# narsil.net
KiCad netlist of a schematic drawn in EAGLE
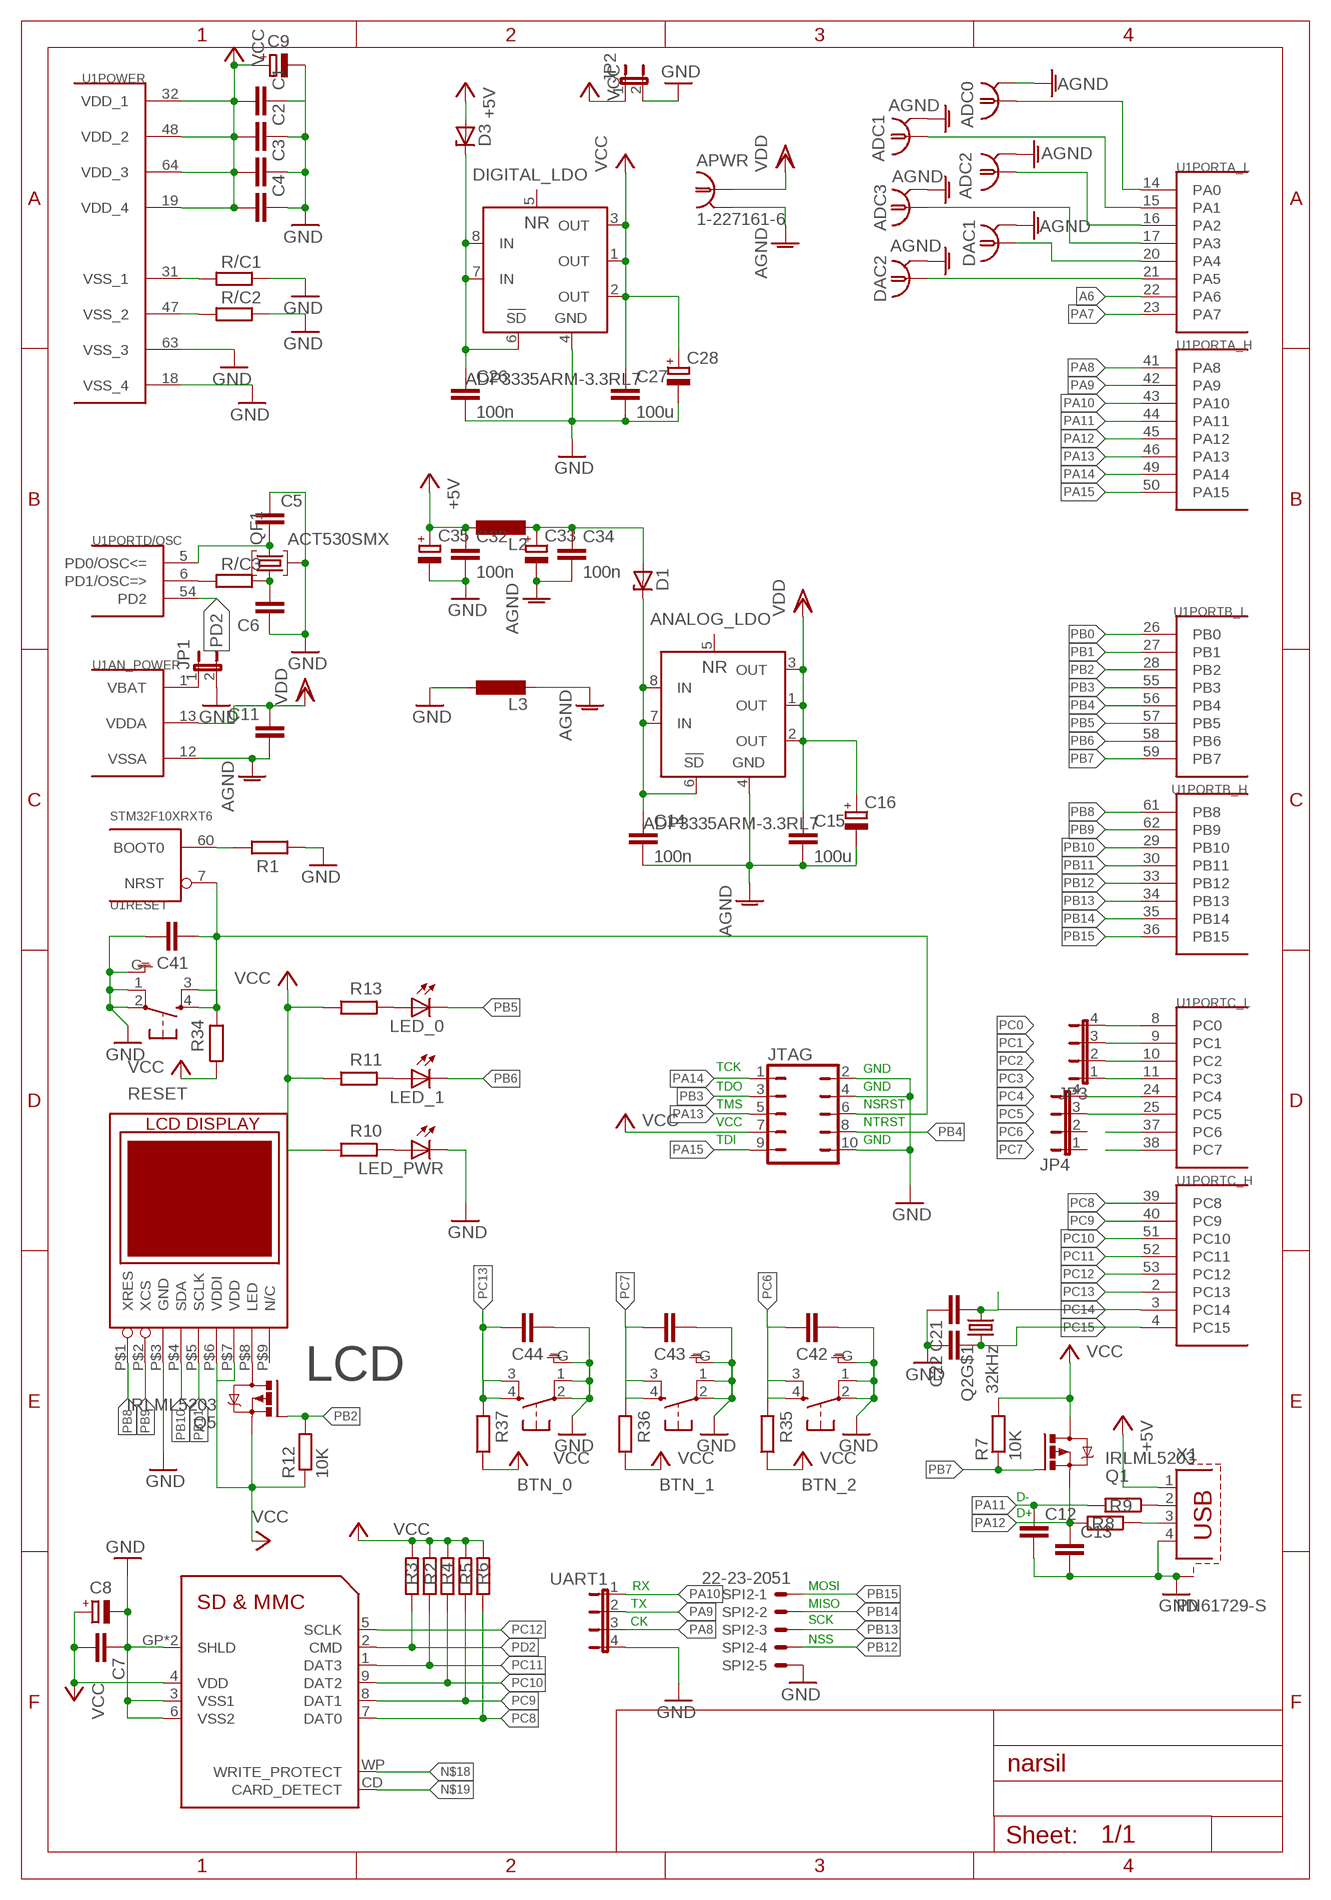
[diagram p0: schematic, sheet 1]

(export (version "E")
  (design (tool "Eeschema 10.0.6"))
  (components
    (comp (ref "ADC0")
      (value "1-227161-6")
      (footprint "eagle-import:AMP_227161")
      (fields (field (name "MF") "TYCO ELECTRONICS"))
      (libsource (lib "eagle-import") (part "?2271611--6"))
    )
    (comp (ref "ADC1")
      (value "1-227161-6")
      (footprint "eagle-import:AMP_227161")
      (fields (field (name "MF") "TYCO ELECTRONICS"))
      (libsource (lib "eagle-import") (part "?2271611--6"))
    )
    (comp (ref "ADC2")
      (value "1-227161-6")
      (footprint "eagle-import:AMP_227161")
      (fields (field (name "MF") "TYCO ELECTRONICS"))
      (libsource (lib "eagle-import") (part "?2271611--6"))
    )
    (comp (ref "ADC3")
      (value "1-227161-6")
      (footprint "eagle-import:AMP_227161")
      (fields
        (field (name "MF") "TYCO ELECTRONICS")
        (field (name "MF_1") "TYCO ELECTRONICS")
        (field (name "MPN") "1-227161-6")
        (field (name "OC_FARNELL") "unknown")
        (field (name "OC_NEWARK") "09H7854")
      )
      (libsource (lib "eagle-import") (part "?2271611--6"))
    )
    (comp (ref "ANALOG_LDO")
      (value "ADP3335ARM-3.3RL7")
      (footprint "eagle-import:MSOP08")
      (libsource (lib "eagle-import") (part "ADP3335ARM-3.3RL7"))
    )
    (comp (ref "APWR")
      (value "1-227161-6")
      (footprint "eagle-import:AMP_227161")
      (fields (field (name "MF") "TYCO ELECTRONICS"))
      (libsource (lib "eagle-import") (part "?2271611--6"))
    )
    (comp (ref "BTN_0")
      (value "10-XXG")
      (footprint "eagle-import:B3F-10XXG")
      (libsource (lib "eagle-import") (part "10-XXG"))
    )
    (comp (ref "BTN_1")
      (value "10-XXG")
      (footprint "eagle-import:B3F-10XXG")
      (libsource (lib "eagle-import") (part "10-XXG"))
    )
    (comp (ref "BTN_2")
      (value "10-XXG")
      (footprint "eagle-import:B3F-10XXG")
      (libsource (lib "eagle-import") (part "10-XXG"))
    )
    (comp (ref "C1")
      (value "C-EUC0805")
      (footprint "eagle-import:C0805")
      (libsource (lib "eagle-import") (part "resistor_C-EUC0805"))
    )
    (comp (ref "C2")
      (value "C-EUC0805")
      (footprint "eagle-import:C0805")
      (libsource (lib "eagle-import") (part "resistor_C-EUC0805"))
    )
    (comp (ref "C3")
      (value "C-EUC0805")
      (footprint "eagle-import:C0805")
      (libsource (lib "eagle-import") (part "resistor_C-EUC0805"))
    )
    (comp (ref "C4")
      (value "C-EUC0805")
      (footprint "eagle-import:C0805")
      (libsource (lib "eagle-import") (part "resistor_C-EUC0805"))
    )
    (comp (ref "C5")
      (value "C-EUC0805")
      (footprint "eagle-import:C0805")
      (libsource (lib "eagle-import") (part "resistor_C-EUC0805"))
    )
    (comp (ref "C6")
      (value "C-EUC0805")
      (footprint "eagle-import:C0805")
      (libsource (lib "eagle-import") (part "resistor_C-EUC0805"))
    )
    (comp (ref "C7")
      (value "C-EUC0805")
      (footprint "eagle-import:C0805")
      (libsource (lib "eagle-import") (part "resistor_C-EUC0805"))
    )
    (comp (ref "C8")
      (value "CPOL-EUSMCA")
      (footprint "eagle-import:SMC_A")
      (libsource (lib "eagle-import") (part "CPOL-EUSMCA"))
    )
    (comp (ref "C9")
      (value "CPOL-EUSMCA")
      (footprint "eagle-import:SMC_A")
      (libsource (lib "eagle-import") (part "CPOL-EUSMCA"))
    )
    (comp (ref "C11")
      (value "C-EUC0805")
      (footprint "eagle-import:C0805")
      (libsource (lib "eagle-import") (part "resistor_C-EUC0805"))
    )
    (comp (ref "C12")
      (value "C-EUC0805")
      (footprint "eagle-import:C0805")
      (libsource (lib "eagle-import") (part "resistor_C-EUC0805"))
    )
    (comp (ref "C13")
      (value "C-EUC0805")
      (footprint "eagle-import:C0805")
      (libsource (lib "eagle-import") (part "resistor_C-EUC0805"))
    )
    (comp (ref "C14")
      (value "100n")
      (footprint "eagle-import:C0805")
      (libsource (lib "eagle-import") (part "C-EUC0805"))
    )
    (comp (ref "C15")
      (value "100u")
      (footprint "eagle-import:C0805")
      (libsource (lib "eagle-import") (part "C-EUC0805"))
    )
    (comp (ref "C16")
      (value "CPOL-EUSMCA")
      (footprint "eagle-import:SMC_A")
      (libsource (lib "eagle-import") (part "CPOL-EUSMCA"))
    )
    (comp (ref "C21")
      (value "C-EUC0805")
      (footprint "eagle-import:C0805")
      (libsource (lib "eagle-import") (part "resistor_C-EUC0805"))
    )
    (comp (ref "C22")
      (value "C-EUC0805")
      (footprint "eagle-import:C0805")
      (libsource (lib "eagle-import") (part "resistor_C-EUC0805"))
    )
    (comp (ref "C26")
      (value "100n")
      (footprint "eagle-import:C0805")
      (libsource (lib "eagle-import") (part "C-EUC0805"))
    )
    (comp (ref "C27")
      (value "100u")
      (footprint "eagle-import:C0805")
      (libsource (lib "eagle-import") (part "C-EUC0805"))
    )
    (comp (ref "C28")
      (value "CPOL-EUSMCA")
      (footprint "eagle-import:SMC_A")
      (libsource (lib "eagle-import") (part "CPOL-EUSMCA"))
    )
    (comp (ref "C32")
      (value "100n")
      (footprint "eagle-import:C0805")
      (libsource (lib "eagle-import") (part "resistor_C-EUC0805"))
    )
    (comp (ref "C33")
      (value "CPOL-EUSMCA")
      (footprint "eagle-import:SMC_A")
      (libsource (lib "eagle-import") (part "CPOL-EUSMCA"))
    )
    (comp (ref "C34")
      (value "100n")
      (footprint "eagle-import:C0805")
      (libsource (lib "eagle-import") (part "resistor_C-EUC0805"))
    )
    (comp (ref "C35")
      (value "CPOL-EUSMCA")
      (footprint "eagle-import:SMC_A")
      (libsource (lib "eagle-import") (part "CPOL-EUSMCA"))
    )
    (comp (ref "C41")
      (value "C-EUC0805")
      (footprint "eagle-import:C0805")
      (libsource (lib "eagle-import") (part "resistor_C-EUC0805"))
    )
    (comp (ref "C42")
      (value "C-EUC0805")
      (footprint "eagle-import:C0805")
      (libsource (lib "eagle-import") (part "resistor_C-EUC0805"))
    )
    (comp (ref "C43")
      (value "C-EUC0805")
      (footprint "eagle-import:C0805")
      (libsource (lib "eagle-import") (part "resistor_C-EUC0805"))
    )
    (comp (ref "C44")
      (value "C-EUC0805")
      (footprint "eagle-import:C0805")
      (libsource (lib "eagle-import") (part "resistor_C-EUC0805"))
    )
    (comp (ref "D1")
      (value "ZENER-DIODESMB")
      (footprint "eagle-import:SMB")
      (libsource (lib "eagle-import") (part "ZENER-DIODESMB"))
    )
    (comp (ref "D3")
      (value "ZENER-DIODESMB")
      (footprint "eagle-import:SMB")
      (libsource (lib "eagle-import") (part "ZENER-DIODESMB"))
    )
    (comp (ref "DAC1")
      (value "1-227161-6")
      (footprint "eagle-import:AMP_227161")
      (fields (field (name "MF") "TYCO ELECTRONICS"))
      (libsource (lib "eagle-import") (part "?2271611--6"))
    )
    (comp (ref "DAC2")
      (value "1-227161-6")
      (footprint "eagle-import:AMP_227161")
      (fields (field (name "MF") "TYCO ELECTRONICS"))
      (libsource (lib "eagle-import") (part "?2271611--6"))
    )
    (comp (ref "DIGITAL_LDO")
      (value "ADP3335ARM-3.3RL7")
      (footprint "eagle-import:MSOP08")
      (libsource (lib "eagle-import") (part "ADP3335ARM-3.3RL7"))
    )
    (comp (ref "JP1")
      (value "JP1E")
      (footprint "eagle-import:JP1")
      (libsource (lib "eagle-import") (part "JP1E"))
    )
    (comp (ref "JP2")
      (value "JP1E")
      (footprint "eagle-import:JP1")
      (libsource (lib "eagle-import") (part "JP1E"))
    )
    (comp (ref "JP3")
      (value "JP4E")
      (footprint "eagle-import:JP4")
      (libsource (lib "eagle-import") (part "JP4E"))
    )
    (comp (ref "JP4")
      (value "JP4E")
      (footprint "eagle-import:JP4")
      (libsource (lib "eagle-import") (part "JP4E"))
    )
    (comp (ref "JTAG")
      (value "JP5Q")
      (footprint "eagle-import:JP5Q")
      (libsource (lib "eagle-import") (part "JP5Q"))
    )
    (comp (ref "L2")
      (value "L-EUL1206")
      (footprint "eagle-import:R1206")
      (libsource (lib "eagle-import") (part "L-EUL1206"))
    )
    (comp (ref "L3")
      (value "L-EUL1206")
      (footprint "eagle-import:R1206")
      (libsource (lib "eagle-import") (part "L-EUL1206"))
    )
    (comp (ref "LED_0")
      (value "LEDSMT1206")
      (footprint "eagle-import:1206")
      (libsource (lib "eagle-import") (part "LEDSMT1206"))
    )
    (comp (ref "LED_1")
      (value "LEDSMT1206")
      (footprint "eagle-import:1206")
      (libsource (lib "eagle-import") (part "LEDSMT1206"))
    )
    (comp (ref "LED_PWR")
      (value "LEDSMT1206")
      (footprint "eagle-import:1206")
      (libsource (lib "eagle-import") (part "LEDSMT1206"))
    )
    (comp (ref "Q1")
      (value "IRLML5203")
      (footprint "eagle-import:MICRO3")
      (libsource (lib "eagle-import") (part "IRLML5203"))
    )
    (comp (ref "Q2")
      (value "32kHz")
      (footprint "eagle-import:MC146")
      (libsource (lib "eagle-import") (part "MC146"))
    )
    (comp (ref "Q5")
      (value "IRLML5203")
      (footprint "eagle-import:MICRO3")
      (libsource (lib "eagle-import") (part "IRLML5203"))
    )
    (comp (ref "QF1")
      (value "ACT530SMX")
      (footprint "eagle-import:ACT530SMX")
      (libsource (lib "eagle-import") (part "ACT530SMX"))
    )
    (comp (ref "R/C1")
      (value "R-EU_M0805")
      (footprint "eagle-import:M0805")
      (libsource (lib "eagle-import") (part "R-EU_M0805"))
    )
    (comp (ref "R/C2")
      (value "R-EU_M0805")
      (footprint "eagle-import:M0805")
      (libsource (lib "eagle-import") (part "R-EU_M0805"))
    )
    (comp (ref "R/C3")
      (value "R-EU_M0805")
      (footprint "eagle-import:M0805")
      (libsource (lib "eagle-import") (part "R-EU_M0805"))
    )
    (comp (ref "R1")
      (value "5k")
      (footprint "eagle-import:M0805")
      (libsource (lib "eagle-import") (part "R-EU_M0805"))
    )
    (comp (ref "R2")
      (value "47k")
      (footprint "eagle-import:M0805")
      (libsource (lib "eagle-import") (part "R-EU_M0805"))
    )
    (comp (ref "R3")
      (value "47k")
      (footprint "eagle-import:M0805")
      (libsource (lib "eagle-import") (part "R-EU_M0805"))
    )
    (comp (ref "R4")
      (value "47k")
      (footprint "eagle-import:M0805")
      (libsource (lib "eagle-import") (part "R-EU_M0805"))
    )
    (comp (ref "R5")
      (value "47k")
      (footprint "eagle-import:M0805")
      (libsource (lib "eagle-import") (part "R-EU_M0805"))
    )
    (comp (ref "R6")
      (value "47k")
      (footprint "eagle-import:M0805")
      (libsource (lib "eagle-import") (part "R-EU_M0805"))
    )
    (comp (ref "R7")
      (value "10K")
      (footprint "eagle-import:M0805")
      (libsource (lib "eagle-import") (part "R-EU_M0805"))
    )
    (comp (ref "R8")
      (value "47k")
      (footprint "eagle-import:M0805")
      (libsource (lib "eagle-import") (part "R-EU_M0805"))
    )
    (comp (ref "R9")
      (value "47k")
      (footprint "eagle-import:M0805")
      (libsource (lib "eagle-import") (part "R-EU_M0805"))
    )
    (comp (ref "R10")
      (value "5k")
      (footprint "eagle-import:M0805")
      (libsource (lib "eagle-import") (part "R-EU_M0805"))
    )
    (comp (ref "R11")
      (value "5k")
      (footprint "eagle-import:M0805")
      (libsource (lib "eagle-import") (part "R-EU_M0805"))
    )
    (comp (ref "R12")
      (value "10K")
      (footprint "eagle-import:M0805")
      (libsource (lib "eagle-import") (part "R-EU_M0805"))
    )
    (comp (ref "R13")
      (value "5k")
      (footprint "eagle-import:M0805")
      (libsource (lib "eagle-import") (part "R-EU_M0805"))
    )
    (comp (ref "R34")
      (value "5k")
      (footprint "eagle-import:M0805")
      (libsource (lib "eagle-import") (part "R-EU_M0805"))
    )
    (comp (ref "R35")
      (value "5k")
      (footprint "eagle-import:M0805")
      (libsource (lib "eagle-import") (part "R-EU_M0805"))
    )
    (comp (ref "R36")
      (value "5k")
      (footprint "eagle-import:M0805")
      (libsource (lib "eagle-import") (part "R-EU_M0805"))
    )
    (comp (ref "R37")
      (value "5k")
      (footprint "eagle-import:M0805")
      (libsource (lib "eagle-import") (part "R-EU_M0805"))
    )
    (comp (ref "RESET")
      (value "10-XXG")
      (footprint "eagle-import:B3F-10XXG")
      (libsource (lib "eagle-import") (part "10-XXG"))
    )
    (comp (ref "SPI2")
      (value "22-23-2051")
      (footprint "eagle-import:22-23-2051")
      (fields (field (name "MF") "MOLEX"))
      (libsource (lib "eagle-import") (part "22-23-2051"))
    )
    (comp (ref "U$1")
      (value "SD-RSMT-2-MQ")
      (footprint "eagle-import:SD-RSMT-2-MQ")
      (libsource (lib "eagle-import") (part "SD-RSMT-2-MQ"))
    )
    (comp (ref "U$2")
      (value "LCD")
      (footprint "eagle-import:LCD_NOKIA1100")
      (libsource (lib "eagle-import") (part "LCD"))
    )
    (comp (ref "U1")
      (value "STM32F10XRXT6")
      (footprint "eagle-import:TQFP64")
      (libsource (lib "eagle-import") (part "STM32F10XRXT6"))
    )
    (comp (ref "UART1")
      (value "JP4E")
      (footprint "eagle-import:JP4")
      (libsource (lib "eagle-import") (part "JP4E"))
    )
    (comp (ref "X1")
      (value "PN61729-S")
      (footprint "eagle-import:PN61729-S")
      (libsource (lib "eagle-import") (part "PN61729-S"))
    )
  )
  (nets
    (net (code "1") (name "+5V") (class "Default")
      (node (ref "C32") (pin "1") (pinfunction "1_1") (pintype "passive"))
      (node (ref "C35") (pin "+") (pinfunction "+_+") (pintype "passive"))
      (node (ref "D3") (pin "A") (pinfunction "A_A") (pintype "passive"))
      (node (ref "L2") (pin "1") (pinfunction "1_1") (pintype "passive"))
      (node (ref "X1") (pin "1") (pinfunction "1_1") (pintype "passive"))
    )
    (net (code "2") (name "A6") (class "Default")
      (node (ref "U1") (pin "22") (pinfunction "PA6_22") (pintype "bidirectional"))
    )
    (net (code "3") (name "AGND") (class "Default")
      (node (ref "ADC0") (pin "2") (pinfunction "GND_2") (pintype "power_in"))
      (node (ref "ADC1") (pin "2") (pinfunction "GND_2") (pintype "power_in"))
      (node (ref "ADC2") (pin "2") (pinfunction "GND_2") (pintype "power_in"))
      (node (ref "ADC3") (pin "2") (pinfunction "GND_2") (pintype "power_in"))
      (node (ref "ANALOG_LDO") (pin "4") (pinfunction "GND_4") (pintype "power_in"))
      (node (ref "APWR") (pin "2") (pinfunction "GND_2") (pintype "power_in"))
      (node (ref "C11") (pin "2") (pinfunction "2_2") (pintype "passive"))
      (node (ref "C14") (pin "2") (pinfunction "2_2") (pintype "passive"))
      (node (ref "C15") (pin "2") (pinfunction "2_2") (pintype "passive"))
      (node (ref "C16") (pin "-") (pinfunction "-_-") (pintype "passive"))
      (node (ref "C33") (pin "-") (pinfunction "-_-") (pintype "passive"))
      (node (ref "C34") (pin "2") (pinfunction "2_2") (pintype "passive"))
      (node (ref "DAC1") (pin "2") (pinfunction "GND_2") (pintype "power_in"))
      (node (ref "DAC2") (pin "2") (pinfunction "GND_2") (pintype "power_in"))
      (node (ref "L3") (pin "2") (pinfunction "2_2") (pintype "passive"))
      (node (ref "U1") (pin "12") (pinfunction "VSSA_12") (pintype "power_in"))
    )
    (net (code "4") (name "GND") (class "Default")
      (node (ref "BTN_0") (pin "1") (pinfunction "P1_1") (pintype "passive"))
      (node (ref "BTN_0") (pin "2") (pinfunction "P_2") (pintype "passive"))
      (node (ref "BTN_0") (pin "G") (pinfunction "GND_G") (pintype "power_in"))
      (node (ref "BTN_1") (pin "1") (pinfunction "P1_1") (pintype "passive"))
      (node (ref "BTN_1") (pin "2") (pinfunction "P_2") (pintype "passive"))
      (node (ref "BTN_1") (pin "G") (pinfunction "GND_G") (pintype "power_in"))
      (node (ref "BTN_2") (pin "1") (pinfunction "P1_1") (pintype "passive"))
      (node (ref "BTN_2") (pin "2") (pinfunction "P_2") (pintype "passive"))
      (node (ref "BTN_2") (pin "G") (pinfunction "GND_G") (pintype "power_in"))
      (node (ref "C1") (pin "1") (pinfunction "1_1") (pintype "passive"))
      (node (ref "C12") (pin "2") (pinfunction "2_2") (pintype "passive"))
      (node (ref "C13") (pin "2") (pinfunction "2_2") (pintype "passive"))
      (node (ref "C2") (pin "1") (pinfunction "1_1") (pintype "passive"))
      (node (ref "C21") (pin "1") (pinfunction "1_1") (pintype "passive"))
      (node (ref "C22") (pin "1") (pinfunction "1_1") (pintype "passive"))
      (node (ref "C26") (pin "2") (pinfunction "2_2") (pintype "passive"))
      (node (ref "C27") (pin "2") (pinfunction "2_2") (pintype "passive"))
      (node (ref "C28") (pin "-") (pinfunction "-_-") (pintype "passive"))
      (node (ref "C3") (pin "1") (pinfunction "1_1") (pintype "passive"))
      (node (ref "C32") (pin "2") (pinfunction "2_2") (pintype "passive"))
      (node (ref "C35") (pin "-") (pinfunction "-_-") (pintype "passive"))
      (node (ref "C4") (pin "1") (pinfunction "1_1") (pintype "passive"))
      (node (ref "C41") (pin "1") (pinfunction "1_1") (pintype "passive"))
      (node (ref "C42") (pin "1") (pinfunction "1_1") (pintype "passive"))
      (node (ref "C43") (pin "1") (pinfunction "1_1") (pintype "passive"))
      (node (ref "C44") (pin "1") (pinfunction "1_1") (pintype "passive"))
      (node (ref "C5") (pin "1") (pinfunction "1_1") (pintype "passive"))
      (node (ref "C6") (pin "1") (pinfunction "1_1") (pintype "passive"))
      (node (ref "C7") (pin "1") (pinfunction "1_1") (pintype "passive"))
      (node (ref "C8") (pin "-") (pinfunction "-_-") (pintype "passive"))
      (node (ref "C9") (pin "-") (pinfunction "-_-") (pintype "passive"))
      (node (ref "DIGITAL_LDO") (pin "4") (pinfunction "GND_4") (pintype "power_in"))
      (node (ref "JP1") (pin "2") (pinfunction "2_2") (pintype "passive"))
      (node (ref "JP2") (pin "2") (pinfunction "2_2") (pintype "passive"))
      (node (ref "JTAG") (pin "10") (pinfunction "10_10") (pintype "passive"))
      (node (ref "JTAG") (pin "2") (pinfunction "2_2") (pintype "passive"))
      (node (ref "JTAG") (pin "4") (pinfunction "4_4") (pintype "passive"))
      (node (ref "L3") (pin "1") (pinfunction "1_1") (pintype "passive"))
      (node (ref "LED_PWR") (pin "C") (pinfunction "C_C") (pintype "passive"))
      (node (ref "QF1") (pin "S$1") (pinfunction "2_S$1") (pintype "passive"))
      (node (ref "QF1") (pin "S$2") (pinfunction "2_S$2") (pintype "passive"))
      (node (ref "R/C1") (pin "1") (pinfunction "1_1") (pintype "passive"))
      (node (ref "R/C2") (pin "1") (pinfunction "1_1") (pintype "passive"))
      (node (ref "R1") (pin "1") (pinfunction "1_1") (pintype "passive"))
      (node (ref "RESET") (pin "1") (pinfunction "P1_1") (pintype "passive"))
      (node (ref "RESET") (pin "2") (pinfunction "P_2") (pintype "passive"))
      (node (ref "RESET") (pin "G") (pinfunction "GND_G") (pintype "power_in"))
      (node (ref "SPI2") (pin "5") (pinfunction "S_5") (pintype "passive"))
      (node (ref "U$1") (pin "3") (pinfunction "VSS1_3") (pintype "power_in"))
      (node (ref "U$1") (pin "6") (pinfunction "VSS2_6") (pintype "power_in"))
      (node (ref "U$1") (pin "GP") (pinfunction "SHLD_GP") (pintype "power_in"))
      (node (ref "U$1") (pin "GP2") (pinfunction "SHLD_GP2") (pintype "power_in"))
      (node (ref "U$2") (pin "P$3") (pinfunction "GND_P$3") (pintype "power_in"))
      (node (ref "U1") (pin "18") (pinfunction "VSS_4_18") (pintype "power_in"))
      (node (ref "U1") (pin "63") (pinfunction "VSS_3_63") (pintype "power_in"))
      (node (ref "UART1") (pin "4") (pinfunction "4_4") (pintype "passive"))
      (node (ref "X1") (pin "4") (pinfunction "4_4") (pintype "passive"))
      (node (ref "X1") (pin "SHLD@1") (pinfunction "S1_SHLD@1") (pintype "passive"))
      (node (ref "X1") (pin "SHLD@2") (pinfunction "S1_SHLD@2") (pintype "passive"))
    )
    (net (code "5") (name "N$18") (class "Default")
      (node (ref "U$1") (pin "WP") (pinfunction "WRITE_PROTECT_WP") (pintype "passive"))
    )
    (net (code "6") (name "N$19") (class "Default")
      (node (ref "U$1") (pin "CD") (pinfunction "CARD_DETECT_CD") (pintype "passive"))
    )
    (net (code "7") (name "Net-(ANALOG_LDO-SD{slash})") (class "Default")
      (node (ref "ANALOG_LDO") (pin "6") (pinfunction "SD/_6") (pintype "input"))
      (node (ref "ANALOG_LDO") (pin "7") (pinfunction "IN_7") (pintype "input"))
      (node (ref "ANALOG_LDO") (pin "8") (pinfunction "IN_8") (pintype "input"))
      (node (ref "C14") (pin "1") (pinfunction "1_1") (pintype "passive"))
      (node (ref "D1") (pin "C") (pinfunction "C_C") (pintype "passive"))
    )
    (net (code "8") (name "Net-(C33-Pad+)") (class "Default")
      (node (ref "C33") (pin "+") (pinfunction "+_+") (pintype "passive"))
      (node (ref "C34") (pin "1") (pinfunction "1_1") (pintype "passive"))
      (node (ref "D1") (pin "A") (pinfunction "A_A") (pintype "passive"))
      (node (ref "L2") (pin "2") (pinfunction "2_2") (pintype "passive"))
    )
    (net (code "9") (name "Net-(DIGITAL_LDO-SD{slash})") (class "Default")
      (node (ref "C26") (pin "1") (pinfunction "1_1") (pintype "passive"))
      (node (ref "D3") (pin "C") (pinfunction "C_C") (pintype "passive"))
      (node (ref "DIGITAL_LDO") (pin "6") (pinfunction "SD/_6") (pintype "input"))
      (node (ref "DIGITAL_LDO") (pin "7") (pinfunction "IN_7") (pintype "input"))
      (node (ref "DIGITAL_LDO") (pin "8") (pinfunction "IN_8") (pintype "input"))
    )
    (net (code "10") (name "Net-(LED_0-PadA)") (class "Default")
      (node (ref "LED_0") (pin "A") (pinfunction "A_A") (pintype "passive"))
      (node (ref "R13") (pin "2") (pinfunction "2_2") (pintype "passive"))
    )
    (net (code "11") (name "Net-(LED_1-PadA)") (class "Default")
      (node (ref "LED_1") (pin "A") (pinfunction "A_A") (pintype "passive"))
      (node (ref "R11") (pin "2") (pinfunction "2_2") (pintype "passive"))
    )
    (net (code "12") (name "Net-(LED_PWR-PadA)") (class "Default")
      (node (ref "LED_PWR") (pin "A") (pinfunction "A_A") (pintype "passive"))
      (node (ref "R10") (pin "2") (pinfunction "2_2") (pintype "passive"))
    )
    (net (code "13") (name "Net-(Q5-D)") (class "Default")
      (node (ref "Q5") (pin "3") (pinfunction "D_3") (pintype "passive"))
      (node (ref "U$2") (pin "P$8") (pinfunction "LED_P$8") (pintype "power_in"))
    )
    (net (code "14") (name "Net-(QF1-1)") (class "Default")
      (node (ref "C6") (pin "2") (pinfunction "2_2") (pintype "passive"))
      (node (ref "QF1") (pin "P1") (pinfunction "1_P1") (pintype "passive"))
      (node (ref "R/C3") (pin "1") (pinfunction "1_1") (pintype "passive"))
    )
    (net (code "15") (name "Net-(QF1-3)") (class "Default")
      (node (ref "C5") (pin "2") (pinfunction "2_2") (pintype "passive"))
      (node (ref "QF1") (pin "P2") (pinfunction "3_P2") (pintype "passive"))
      (node (ref "U1") (pin "5") (pinfunction "PD0/OSC<=_5") (pintype "bidirectional"))
    )
    (net (code "16") (name "Net-(R8-Pad1)") (class "Default")
      (node (ref "R8") (pin "1") (pinfunction "1_1") (pintype "passive"))
      (node (ref "X1") (pin "3") (pinfunction "3_3") (pintype "passive"))
    )
    (net (code "17") (name "Net-(R9-Pad1)") (class "Default")
      (node (ref "R9") (pin "1") (pinfunction "1_1") (pintype "passive"))
      (node (ref "X1") (pin "2") (pinfunction "2_2") (pintype "passive"))
    )
    (net (code "18") (name "Net-(RESET-S)") (class "Default")
      (node (ref "C41") (pin "2") (pinfunction "2_2") (pintype "passive"))
      (node (ref "JTAG") (pin "6") (pinfunction "6_6") (pintype "passive"))
      (node (ref "R34") (pin "2") (pinfunction "2_2") (pintype "passive"))
      (node (ref "RESET") (pin "3") (pinfunction "S1_3") (pintype "passive"))
      (node (ref "RESET") (pin "4") (pinfunction "S_4") (pintype "passive"))
      (node (ref "U1") (pin "7") (pinfunction "NRST_7") (pintype "input"))
    )
    (net (code "19") (name "Net-(U1A-VBAT)") (class "Default")
      (node (ref "JP1") (pin "1") (pinfunction "1_1") (pintype "passive"))
      (node (ref "U1") (pin "1") (pinfunction "VBAT_1") (pintype "power_in"))
    )
    (net (code "20") (name "Net-(U1C-PA0)") (class "Default")
      (node (ref "ADC0") (pin "1") (pinfunction "1_1") (pintype "passive"))
      (node (ref "U1") (pin "14") (pinfunction "PA0_14") (pintype "bidirectional"))
    )
    (net (code "21") (name "Net-(U1C-PA1)") (class "Default")
      (node (ref "ADC1") (pin "1") (pinfunction "1_1") (pintype "passive"))
      (node (ref "U1") (pin "15") (pinfunction "PA1_15") (pintype "bidirectional"))
    )
    (net (code "22") (name "Net-(U1C-PA2)") (class "Default")
      (node (ref "ADC2") (pin "1") (pinfunction "1_1") (pintype "passive"))
      (node (ref "U1") (pin "16") (pinfunction "PA2_16") (pintype "bidirectional"))
    )
    (net (code "23") (name "Net-(U1C-PA3)") (class "Default")
      (node (ref "ADC3") (pin "1") (pinfunction "1_1") (pintype "passive"))
      (node (ref "U1") (pin "17") (pinfunction "PA3_17") (pintype "bidirectional"))
    )
    (net (code "24") (name "Net-(U1C-PA4)") (class "Default")
      (node (ref "DAC1") (pin "1") (pinfunction "1_1") (pintype "passive"))
      (node (ref "U1") (pin "20") (pinfunction "PA4_20") (pintype "bidirectional"))
    )
    (net (code "25") (name "Net-(U1C-PA5)") (class "Default")
      (node (ref "DAC2") (pin "1") (pinfunction "1_1") (pintype "passive"))
      (node (ref "U1") (pin "21") (pinfunction "PA5_21") (pintype "bidirectional"))
    )
    (net (code "26") (name "Net-(U1H-PD1{slash}OSC=>)") (class "Default")
      (node (ref "R/C3") (pin "2") (pinfunction "2_2") (pintype "passive"))
      (node (ref "U1") (pin "6") (pinfunction "PD1/OSC=>_6") (pintype "bidirectional"))
    )
    (net (code "27") (name "Net-(U1I-VSS_1)") (class "Default")
      (node (ref "R/C1") (pin "2") (pinfunction "2_2") (pintype "passive"))
      (node (ref "U1") (pin "31") (pinfunction "VSS_1_31") (pintype "power_in"))
    )
    (net (code "28") (name "Net-(U1I-VSS_2)") (class "Default")
      (node (ref "R/C2") (pin "2") (pinfunction "2_2") (pintype "passive"))
      (node (ref "U1") (pin "47") (pinfunction "VSS_2_47") (pintype "power_in"))
    )
    (net (code "29") (name "Net-(U1J-BOOT0)") (class "Default")
      (node (ref "R1") (pin "2") (pinfunction "2_2") (pintype "passive"))
      (node (ref "U1") (pin "60") (pinfunction "BOOT0_60") (pintype "input"))
    )
    (net (code "30") (name "PA7") (class "Default")
      (node (ref "U1") (pin "23") (pinfunction "PA7_23") (pintype "bidirectional"))
    )
    (net (code "31") (name "PA8") (class "Default")
      (node (ref "U1") (pin "41") (pinfunction "PA8_41") (pintype "bidirectional"))
      (node (ref "UART1") (pin "3") (pinfunction "3_3") (pintype "passive"))
    )
    (net (code "32") (name "PA9") (class "Default")
      (node (ref "U1") (pin "42") (pinfunction "PA9_42") (pintype "bidirectional"))
      (node (ref "UART1") (pin "2") (pinfunction "2_2") (pintype "passive"))
    )
    (net (code "33") (name "PA10") (class "Default")
      (node (ref "U1") (pin "43") (pinfunction "PA10_43") (pintype "bidirectional"))
      (node (ref "UART1") (pin "1") (pinfunction "1_1") (pintype "passive"))
    )
    (net (code "34") (name "PA11") (class "Default")
      (node (ref "C12") (pin "1") (pinfunction "1_1") (pintype "passive"))
      (node (ref "R9") (pin "2") (pinfunction "2_2") (pintype "passive"))
      (node (ref "U1") (pin "44") (pinfunction "PA11_44") (pintype "bidirectional"))
    )
    (net (code "35") (name "PA12") (class "Default")
      (node (ref "C13") (pin "1") (pinfunction "1_1") (pintype "passive"))
      (node (ref "Q1") (pin "2") (pinfunction "S_2") (pintype "passive"))
      (node (ref "R8") (pin "2") (pinfunction "2_2") (pintype "passive"))
      (node (ref "U1") (pin "45") (pinfunction "PA12_45") (pintype "bidirectional"))
    )
    (net (code "36") (name "PA13") (class "Default")
      (node (ref "JTAG") (pin "5") (pinfunction "5_5") (pintype "passive"))
      (node (ref "U1") (pin "46") (pinfunction "PA13_46") (pintype "bidirectional"))
    )
    (net (code "37") (name "PA14") (class "Default")
      (node (ref "JTAG") (pin "1") (pinfunction "1_1") (pintype "passive"))
      (node (ref "U1") (pin "49") (pinfunction "PA14_49") (pintype "bidirectional"))
    )
    (net (code "38") (name "PA15") (class "Default")
      (node (ref "JTAG") (pin "9") (pinfunction "9_9") (pintype "passive"))
      (node (ref "U1") (pin "50") (pinfunction "PA15_50") (pintype "bidirectional"))
    )
    (net (code "39") (name "PB0") (class "Default")
      (node (ref "U1") (pin "26") (pinfunction "PB0_26") (pintype "bidirectional"))
    )
    (net (code "40") (name "PB1") (class "Default")
      (node (ref "U1") (pin "27") (pinfunction "PB1_27") (pintype "bidirectional"))
    )
    (net (code "41") (name "PB2") (class "Default")
      (node (ref "Q5") (pin "1") (pinfunction "G_1") (pintype "passive"))
      (node (ref "R12") (pin "2") (pinfunction "2_2") (pintype "passive"))
      (node (ref "U1") (pin "28") (pinfunction "PB2_28") (pintype "bidirectional"))
    )
    (net (code "42") (name "PB3") (class "Default")
      (node (ref "JTAG") (pin "3") (pinfunction "3_3") (pintype "passive"))
      (node (ref "U1") (pin "55") (pinfunction "PB3_55") (pintype "bidirectional"))
    )
    (net (code "43") (name "PB4") (class "Default")
      (node (ref "JTAG") (pin "8") (pinfunction "8_8") (pintype "passive"))
      (node (ref "U1") (pin "56") (pinfunction "PB4_56") (pintype "bidirectional"))
    )
    (net (code "44") (name "PB5") (class "Default")
      (node (ref "LED_0") (pin "C") (pinfunction "C_C") (pintype "passive"))
      (node (ref "U1") (pin "57") (pinfunction "PB5_57") (pintype "bidirectional"))
    )
    (net (code "45") (name "PB6") (class "Default")
      (node (ref "LED_1") (pin "C") (pinfunction "C_C") (pintype "passive"))
      (node (ref "U1") (pin "58") (pinfunction "PB6_58") (pintype "bidirectional"))
    )
    (net (code "46") (name "PB7") (class "Default")
      (node (ref "Q1") (pin "1") (pinfunction "G_1") (pintype "passive"))
      (node (ref "R7") (pin "1") (pinfunction "1_1") (pintype "passive"))
      (node (ref "U1") (pin "59") (pinfunction "PB7_59") (pintype "bidirectional"))
    )
    (net (code "47") (name "PB8") (class "Default")
      (node (ref "U$2") (pin "P$1") (pinfunction "XRES_P$1") (pintype "input"))
      (node (ref "U1") (pin "61") (pinfunction "PB8_61") (pintype "bidirectional"))
    )
    (net (code "48") (name "PB9") (class "Default")
      (node (ref "U$2") (pin "P$2") (pinfunction "XCS_P$2") (pintype "input"))
      (node (ref "U1") (pin "62") (pinfunction "PB9_62") (pintype "bidirectional"))
    )
    (net (code "49") (name "PB10") (class "Default")
      (node (ref "U$2") (pin "P$4") (pinfunction "SDA_P$4") (pintype "input"))
      (node (ref "U1") (pin "29") (pinfunction "PB10_29") (pintype "bidirectional"))
    )
    (net (code "50") (name "PB11") (class "Default")
      (node (ref "U$2") (pin "P$5") (pinfunction "SCLK_P$5") (pintype "input"))
      (node (ref "U1") (pin "30") (pinfunction "PB11_30") (pintype "bidirectional"))
    )
    (net (code "51") (name "PB12") (class "Default")
      (node (ref "SPI2") (pin "4") (pinfunction "S_4") (pintype "passive"))
      (node (ref "U1") (pin "33") (pinfunction "PB12_33") (pintype "bidirectional"))
    )
    (net (code "52") (name "PB13") (class "Default")
      (node (ref "SPI2") (pin "3") (pinfunction "S_3") (pintype "passive"))
      (node (ref "U1") (pin "34") (pinfunction "PB13_34") (pintype "bidirectional"))
    )
    (net (code "53") (name "PB14") (class "Default")
      (node (ref "SPI2") (pin "2") (pinfunction "S_2") (pintype "passive"))
      (node (ref "U1") (pin "35") (pinfunction "PB14_35") (pintype "bidirectional"))
    )
    (net (code "54") (name "PB15") (class "Default")
      (node (ref "SPI2") (pin "1") (pinfunction "S_1") (pintype "passive"))
      (node (ref "U1") (pin "36") (pinfunction "PB15_36") (pintype "bidirectional"))
    )
    (net (code "55") (name "PC0") (class "Default")
      (node (ref "JP3") (pin "4") (pinfunction "4_4") (pintype "passive"))
      (node (ref "U1") (pin "8") (pinfunction "PC0_8") (pintype "bidirectional"))
    )
    (net (code "56") (name "PC1") (class "Default")
      (node (ref "JP3") (pin "3") (pinfunction "3_3") (pintype "passive"))
      (node (ref "U1") (pin "9") (pinfunction "PC1_9") (pintype "bidirectional"))
    )
    (net (code "57") (name "PC2") (class "Default")
      (node (ref "JP3") (pin "2") (pinfunction "2_2") (pintype "passive"))
      (node (ref "U1") (pin "10") (pinfunction "PC2_10") (pintype "bidirectional"))
    )
    (net (code "58") (name "PC3") (class "Default")
      (node (ref "JP3") (pin "1") (pinfunction "1_1") (pintype "passive"))
      (node (ref "U1") (pin "11") (pinfunction "PC3_11") (pintype "bidirectional"))
    )
    (net (code "59") (name "PC4") (class "Default")
      (node (ref "JP4") (pin "4") (pinfunction "4_4") (pintype "passive"))
      (node (ref "U1") (pin "24") (pinfunction "PC4_24") (pintype "bidirectional"))
    )
    (net (code "60") (name "PC5") (class "Default")
      (node (ref "JP4") (pin "3") (pinfunction "3_3") (pintype "passive"))
      (node (ref "U1") (pin "25") (pinfunction "PC5_25") (pintype "bidirectional"))
    )
    (net (code "61") (name "PC6") (class "Default")
      (node (ref "BTN_2") (pin "3") (pinfunction "S1_3") (pintype "passive"))
      (node (ref "BTN_2") (pin "4") (pinfunction "S_4") (pintype "passive"))
      (node (ref "C42") (pin "2") (pinfunction "2_2") (pintype "passive"))
      (node (ref "R35") (pin "2") (pinfunction "2_2") (pintype "passive"))
      (node (ref "U1") (pin "37") (pinfunction "PC6_37") (pintype "bidirectional"))
    )
    (net (code "62") (name "PC7") (class "Default")
      (node (ref "BTN_1") (pin "3") (pinfunction "S1_3") (pintype "passive"))
      (node (ref "BTN_1") (pin "4") (pinfunction "S_4") (pintype "passive"))
      (node (ref "C43") (pin "2") (pinfunction "2_2") (pintype "passive"))
      (node (ref "R36") (pin "2") (pinfunction "2_2") (pintype "passive"))
      (node (ref "U1") (pin "38") (pinfunction "PC7_38") (pintype "bidirectional"))
    )
    (net (code "63") (name "PC8") (class "Default")
      (node (ref "R6") (pin "1") (pinfunction "1_1") (pintype "passive"))
      (node (ref "U$1") (pin "7") (pinfunction "DAT0_7") (pintype "output"))
      (node (ref "U1") (pin "39") (pinfunction "PC8_39") (pintype "bidirectional"))
    )
    (net (code "64") (name "PC9") (class "Default")
      (node (ref "R5") (pin "1") (pinfunction "1_1") (pintype "passive"))
      (node (ref "U$1") (pin "8") (pinfunction "DAT1_8") (pintype "bidirectional"))
      (node (ref "U1") (pin "40") (pinfunction "PC9_40") (pintype "bidirectional"))
    )
    (net (code "65") (name "PC10") (class "Default")
      (node (ref "R4") (pin "1") (pinfunction "1_1") (pintype "passive"))
      (node (ref "U$1") (pin "9") (pinfunction "DAT2_9") (pintype "bidirectional"))
      (node (ref "U1") (pin "51") (pinfunction "PC10_51") (pintype "bidirectional"))
    )
    (net (code "66") (name "PC11") (class "Default")
      (node (ref "R2") (pin "1") (pinfunction "1_1") (pintype "passive"))
      (node (ref "U$1") (pin "1") (pinfunction "DAT3_1") (pintype "input"))
      (node (ref "U1") (pin "52") (pinfunction "PC11_52") (pintype "bidirectional"))
    )
    (net (code "67") (name "PC12") (class "Default")
      (node (ref "U$1") (pin "5") (pinfunction "SCLK_5") (pintype "input"))
      (node (ref "U1") (pin "53") (pinfunction "PC12_53") (pintype "bidirectional"))
    )
    (net (code "68") (name "PC13") (class "Default")
      (node (ref "BTN_0") (pin "3") (pinfunction "S1_3") (pintype "passive"))
      (node (ref "BTN_0") (pin "4") (pinfunction "S_4") (pintype "passive"))
      (node (ref "C44") (pin "2") (pinfunction "2_2") (pintype "passive"))
      (node (ref "R37") (pin "2") (pinfunction "2_2") (pintype "passive"))
      (node (ref "U1") (pin "2") (pinfunction "PC13_2") (pintype "bidirectional"))
    )
    (net (code "69") (name "PC14") (class "Default")
      (node (ref "C21") (pin "2") (pinfunction "2_2") (pintype "passive"))
      (node (ref "Q2") (pin "P$1") (pinfunction "1_P$1") (pintype "passive"))
      (node (ref "U1") (pin "3") (pinfunction "PC14_3") (pintype "bidirectional"))
    )
    (net (code "70") (name "PC15") (class "Default")
      (node (ref "C22") (pin "2") (pinfunction "2_2") (pintype "passive"))
      (node (ref "Q2") (pin "P$2") (pinfunction "2_P$2") (pintype "passive"))
      (node (ref "U1") (pin "4") (pinfunction "PC15_4") (pintype "bidirectional"))
    )
    (net (code "71") (name "PD2") (class "Default")
      (node (ref "R3") (pin "1") (pinfunction "1_1") (pintype "passive"))
      (node (ref "U$1") (pin "2") (pinfunction "CMD_2") (pintype "input"))
      (node (ref "U1") (pin "54") (pinfunction "PD2_54") (pintype "bidirectional"))
    )
    (net (code "72") (name "VCC") (class "Default")
      (node (ref "C1") (pin "2") (pinfunction "2_2") (pintype "passive"))
      (node (ref "C2") (pin "2") (pinfunction "2_2") (pintype "passive"))
      (node (ref "C27") (pin "1") (pinfunction "1_1") (pintype "passive"))
      (node (ref "C28") (pin "+") (pinfunction "+_+") (pintype "passive"))
      (node (ref "C3") (pin "2") (pinfunction "2_2") (pintype "passive"))
      (node (ref "C4") (pin "2") (pinfunction "2_2") (pintype "passive"))
      (node (ref "C7") (pin "2") (pinfunction "2_2") (pintype "passive"))
      (node (ref "C8") (pin "+") (pinfunction "+_+") (pintype "passive"))
      (node (ref "C9") (pin "+") (pinfunction "+_+") (pintype "passive"))
      (node (ref "DIGITAL_LDO") (pin "1") (pinfunction "OUT_1") (pintype "passive"))
      (node (ref "DIGITAL_LDO") (pin "2") (pinfunction "OUT_2") (pintype "passive"))
      (node (ref "DIGITAL_LDO") (pin "3") (pinfunction "OUT_3") (pintype "passive"))
      (node (ref "JP2") (pin "1") (pinfunction "1_1") (pintype "passive"))
      (node (ref "JTAG") (pin "7") (pinfunction "7_7") (pintype "passive"))
      (node (ref "Q1") (pin "3") (pinfunction "D_3") (pintype "passive"))
      (node (ref "Q5") (pin "2") (pinfunction "S_2") (pintype "passive"))
      (node (ref "R10") (pin "1") (pinfunction "1_1") (pintype "passive"))
      (node (ref "R11") (pin "1") (pinfunction "1_1") (pintype "passive"))
      (node (ref "R12") (pin "1") (pinfunction "1_1") (pintype "passive"))
      (node (ref "R13") (pin "1") (pinfunction "1_1") (pintype "passive"))
      (node (ref "R2") (pin "2") (pinfunction "2_2") (pintype "passive"))
      (node (ref "R3") (pin "2") (pinfunction "2_2") (pintype "passive"))
      (node (ref "R34") (pin "1") (pinfunction "1_1") (pintype "passive"))
      (node (ref "R35") (pin "1") (pinfunction "1_1") (pintype "passive"))
      (node (ref "R36") (pin "1") (pinfunction "1_1") (pintype "passive"))
      (node (ref "R37") (pin "1") (pinfunction "1_1") (pintype "passive"))
      (node (ref "R4") (pin "2") (pinfunction "2_2") (pintype "passive"))
      (node (ref "R5") (pin "2") (pinfunction "2_2") (pintype "passive"))
      (node (ref "R6") (pin "2") (pinfunction "2_2") (pintype "passive"))
      (node (ref "R7") (pin "2") (pinfunction "2_2") (pintype "passive"))
      (node (ref "U$1") (pin "4") (pinfunction "VDD_4") (pintype "power_in"))
      (node (ref "U$2") (pin "P$6") (pinfunction "VDDI_P$6") (pintype "power_in"))
      (node (ref "U$2") (pin "P$7") (pinfunction "VDD_P$7") (pintype "power_in"))
      (node (ref "U1") (pin "19") (pinfunction "VDD_4_19") (pintype "power_in"))
      (node (ref "U1") (pin "32") (pinfunction "VDD_1_32") (pintype "power_in"))
      (node (ref "U1") (pin "48") (pinfunction "VDD_2_48") (pintype "power_in"))
      (node (ref "U1") (pin "64") (pinfunction "VDD_3_64") (pintype "power_in"))
    )
    (net (code "73") (name "VDD") (class "Default")
      (node (ref "ANALOG_LDO") (pin "1") (pinfunction "OUT_1") (pintype "passive"))
      (node (ref "ANALOG_LDO") (pin "2") (pinfunction "OUT_2") (pintype "passive"))
      (node (ref "ANALOG_LDO") (pin "3") (pinfunction "OUT_3") (pintype "passive"))
      (node (ref "APWR") (pin "1") (pinfunction "1_1") (pintype "passive"))
      (node (ref "C11") (pin "1") (pinfunction "1_1") (pintype "passive"))
      (node (ref "C15") (pin "1") (pinfunction "1_1") (pintype "passive"))
      (node (ref "C16") (pin "+") (pinfunction "+_+") (pintype "passive"))
      (node (ref "U1") (pin "13") (pinfunction "VDDA_13") (pintype "power_in"))
    )
    (net (code "74") (name "unconnected-(ANALOG_LDO-NR-Pad5)") (class "Default")
      (node (ref "ANALOG_LDO") (pin "5") (pinfunction "NR_5") (pintype "passive"))
    )
    (net (code "75") (name "unconnected-(DIGITAL_LDO-NR-Pad5)") (class "Default")
      (node (ref "DIGITAL_LDO") (pin "5") (pinfunction "NR_5") (pintype "passive"))
    )
    (net (code "76") (name "unconnected-(JP4-Pad1)") (class "Default")
      (node (ref "JP4") (pin "1") (pinfunction "1_1") (pintype "passive"))
    )
    (net (code "77") (name "unconnected-(JP4-Pad2)") (class "Default")
      (node (ref "JP4") (pin "2") (pinfunction "2_2") (pintype "passive"))
    )
    (net (code "78") (name "unconnected-(U$2-N{slash}C-PadP$9)") (class "Default")
      (node (ref "U$2") (pin "P$9") (pinfunction "N/C_P$9") (pintype "no_connect"))
    )
  )
)
